# Cookie_Connector.net
KiCad netlist of a schematic drawn in Altium Designer
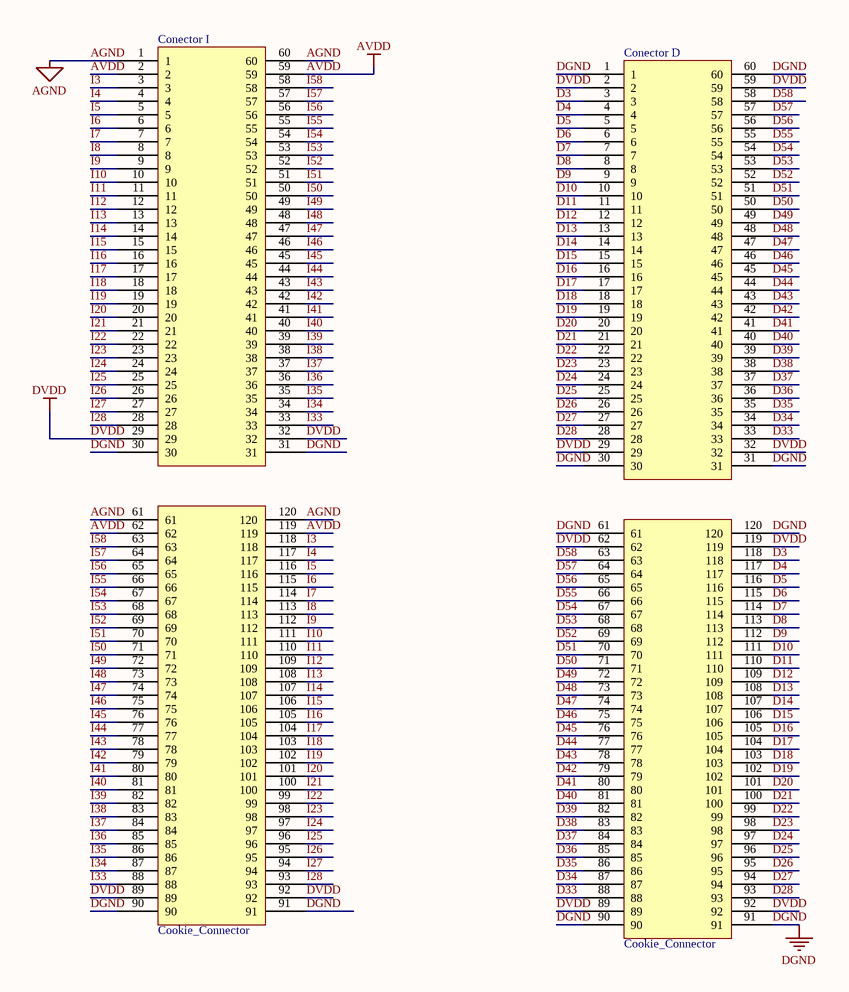
[diagram p0: Cookie Connector.schdoc]

(export (version "E")
  (design (tool "Eeschema 10.0.6"))
  (components
    (comp (ref "Conector D")
      (value "Cookie_Connector")
      (footprint "COOKIECON_HEADER_AND_SOCKET")
      (libsource (lib "Schlib1") (part "Cookie_Connector"))
    )
    (comp (ref "Conector I")
      (value "Cookie_Connector")
      (footprint "COOKIECON_HEADER_AND_SOCKET")
      (libsource (lib "Schlib1") (part "Cookie_Connector"))
    )
  )
  (nets
    (net (code "1") (name "/D3") (class "Default")
      (node (ref "Conector D") (pin "118") (pinfunction "118_118") (pintype "passive"))
      (node (ref "Conector D") (pin "3") (pinfunction "3_3") (pintype "passive"))
    )
    (net (code "2") (name "/D4") (class "Default")
      (node (ref "Conector D") (pin "117") (pinfunction "117_117") (pintype "passive"))
      (node (ref "Conector D") (pin "4") (pinfunction "4_4") (pintype "passive"))
    )
    (net (code "3") (name "/D5") (class "Default")
      (node (ref "Conector D") (pin "116") (pinfunction "116_116") (pintype "passive"))
      (node (ref "Conector D") (pin "5") (pinfunction "5_5") (pintype "passive"))
    )
    (net (code "4") (name "/D6") (class "Default")
      (node (ref "Conector D") (pin "115") (pinfunction "115_115") (pintype "passive"))
      (node (ref "Conector D") (pin "6") (pinfunction "6_6") (pintype "passive"))
    )
    (net (code "5") (name "/D7") (class "Default")
      (node (ref "Conector D") (pin "114") (pinfunction "114_114") (pintype "passive"))
      (node (ref "Conector D") (pin "7") (pinfunction "7_7") (pintype "passive"))
    )
    (net (code "6") (name "/D8") (class "Default")
      (node (ref "Conector D") (pin "113") (pinfunction "113_113") (pintype "passive"))
      (node (ref "Conector D") (pin "8") (pinfunction "8_8") (pintype "passive"))
    )
    (net (code "7") (name "/D9") (class "Default")
      (node (ref "Conector D") (pin "112") (pinfunction "112_112") (pintype "passive"))
      (node (ref "Conector D") (pin "9") (pinfunction "9_9") (pintype "passive"))
    )
    (net (code "8") (name "/D10") (class "Default")
      (node (ref "Conector D") (pin "10") (pinfunction "10_10") (pintype "passive"))
      (node (ref "Conector D") (pin "111") (pinfunction "111_111") (pintype "passive"))
    )
    (net (code "9") (name "/D11") (class "Default")
      (node (ref "Conector D") (pin "11") (pinfunction "11_11") (pintype "passive"))
      (node (ref "Conector D") (pin "110") (pinfunction "110_110") (pintype "passive"))
    )
    (net (code "10") (name "/D12") (class "Default")
      (node (ref "Conector D") (pin "109") (pinfunction "109_109") (pintype "passive"))
      (node (ref "Conector D") (pin "12") (pinfunction "12_12") (pintype "passive"))
    )
    (net (code "11") (name "/D13") (class "Default")
      (node (ref "Conector D") (pin "108") (pinfunction "108_108") (pintype "passive"))
      (node (ref "Conector D") (pin "13") (pinfunction "13_13") (pintype "passive"))
    )
    (net (code "12") (name "/D14") (class "Default")
      (node (ref "Conector D") (pin "107") (pinfunction "107_107") (pintype "passive"))
      (node (ref "Conector D") (pin "14") (pinfunction "14_14") (pintype "passive"))
    )
    (net (code "13") (name "/D15") (class "Default")
      (node (ref "Conector D") (pin "106") (pinfunction "106_106") (pintype "passive"))
      (node (ref "Conector D") (pin "15") (pinfunction "15_15") (pintype "passive"))
    )
    (net (code "14") (name "/D16") (class "Default")
      (node (ref "Conector D") (pin "105") (pinfunction "105_105") (pintype "passive"))
      (node (ref "Conector D") (pin "16") (pinfunction "16_16") (pintype "passive"))
    )
    (net (code "15") (name "/D17") (class "Default")
      (node (ref "Conector D") (pin "104") (pinfunction "104_104") (pintype "passive"))
      (node (ref "Conector D") (pin "17") (pinfunction "17_17") (pintype "passive"))
    )
    (net (code "16") (name "/D18") (class "Default")
      (node (ref "Conector D") (pin "103") (pinfunction "103_103") (pintype "passive"))
      (node (ref "Conector D") (pin "18") (pinfunction "18_18") (pintype "passive"))
    )
    (net (code "17") (name "/D19") (class "Default")
      (node (ref "Conector D") (pin "102") (pinfunction "102_102") (pintype "passive"))
      (node (ref "Conector D") (pin "19") (pinfunction "19_19") (pintype "passive"))
    )
    (net (code "18") (name "/D20") (class "Default")
      (node (ref "Conector D") (pin "101") (pinfunction "101_101") (pintype "passive"))
      (node (ref "Conector D") (pin "20") (pinfunction "20_20") (pintype "passive"))
    )
    (net (code "19") (name "/D21") (class "Default")
      (node (ref "Conector D") (pin "100") (pinfunction "100_100") (pintype "passive"))
      (node (ref "Conector D") (pin "21") (pinfunction "21_21") (pintype "passive"))
    )
    (net (code "20") (name "/D22") (class "Default")
      (node (ref "Conector D") (pin "22") (pinfunction "22_22") (pintype "passive"))
      (node (ref "Conector D") (pin "99") (pinfunction "99_99") (pintype "passive"))
    )
    (net (code "21") (name "/D23") (class "Default")
      (node (ref "Conector D") (pin "23") (pinfunction "23_23") (pintype "passive"))
      (node (ref "Conector D") (pin "98") (pinfunction "98_98") (pintype "passive"))
    )
    (net (code "22") (name "/D24") (class "Default")
      (node (ref "Conector D") (pin "24") (pinfunction "24_24") (pintype "passive"))
      (node (ref "Conector D") (pin "97") (pinfunction "97_97") (pintype "passive"))
    )
    (net (code "23") (name "/D25") (class "Default")
      (node (ref "Conector D") (pin "25") (pinfunction "25_25") (pintype "passive"))
      (node (ref "Conector D") (pin "96") (pinfunction "96_96") (pintype "passive"))
    )
    (net (code "24") (name "/D26") (class "Default")
      (node (ref "Conector D") (pin "26") (pinfunction "26_26") (pintype "passive"))
      (node (ref "Conector D") (pin "95") (pinfunction "95_95") (pintype "passive"))
    )
    (net (code "25") (name "/D27") (class "Default")
      (node (ref "Conector D") (pin "27") (pinfunction "27_27") (pintype "passive"))
      (node (ref "Conector D") (pin "94") (pinfunction "94_94") (pintype "passive"))
    )
    (net (code "26") (name "/D28") (class "Default")
      (node (ref "Conector D") (pin "28") (pinfunction "28_28") (pintype "passive"))
      (node (ref "Conector D") (pin "93") (pinfunction "93_93") (pintype "passive"))
    )
    (net (code "27") (name "/D33") (class "Default")
      (node (ref "Conector D") (pin "33") (pinfunction "33_33") (pintype "passive"))
      (node (ref "Conector D") (pin "88") (pinfunction "88_88") (pintype "passive"))
    )
    (net (code "28") (name "/D34") (class "Default")
      (node (ref "Conector D") (pin "34") (pinfunction "34_34") (pintype "passive"))
      (node (ref "Conector D") (pin "87") (pinfunction "87_87") (pintype "passive"))
    )
    (net (code "29") (name "/D35") (class "Default")
      (node (ref "Conector D") (pin "35") (pinfunction "35_35") (pintype "passive"))
      (node (ref "Conector D") (pin "86") (pinfunction "86_86") (pintype "passive"))
    )
    (net (code "30") (name "/D36") (class "Default")
      (node (ref "Conector D") (pin "36") (pinfunction "36_36") (pintype "passive"))
      (node (ref "Conector D") (pin "85") (pinfunction "85_85") (pintype "passive"))
    )
    (net (code "31") (name "/D37") (class "Default")
      (node (ref "Conector D") (pin "37") (pinfunction "37_37") (pintype "passive"))
      (node (ref "Conector D") (pin "84") (pinfunction "84_84") (pintype "passive"))
    )
    (net (code "32") (name "/D38") (class "Default")
      (node (ref "Conector D") (pin "38") (pinfunction "38_38") (pintype "passive"))
      (node (ref "Conector D") (pin "83") (pinfunction "83_83") (pintype "passive"))
    )
    (net (code "33") (name "/D39") (class "Default")
      (node (ref "Conector D") (pin "39") (pinfunction "39_39") (pintype "passive"))
      (node (ref "Conector D") (pin "82") (pinfunction "82_82") (pintype "passive"))
    )
    (net (code "34") (name "/D40") (class "Default")
      (node (ref "Conector D") (pin "40") (pinfunction "40_40") (pintype "passive"))
      (node (ref "Conector D") (pin "81") (pinfunction "81_81") (pintype "passive"))
    )
    (net (code "35") (name "/D41") (class "Default")
      (node (ref "Conector D") (pin "41") (pinfunction "41_41") (pintype "passive"))
      (node (ref "Conector D") (pin "80") (pinfunction "80_80") (pintype "passive"))
    )
    (net (code "36") (name "/D42") (class "Default")
      (node (ref "Conector D") (pin "42") (pinfunction "42_42") (pintype "passive"))
      (node (ref "Conector D") (pin "79") (pinfunction "79_79") (pintype "passive"))
    )
    (net (code "37") (name "/D43") (class "Default")
      (node (ref "Conector D") (pin "43") (pinfunction "43_43") (pintype "passive"))
      (node (ref "Conector D") (pin "78") (pinfunction "78_78") (pintype "passive"))
    )
    (net (code "38") (name "/D44") (class "Default")
      (node (ref "Conector D") (pin "44") (pinfunction "44_44") (pintype "passive"))
      (node (ref "Conector D") (pin "77") (pinfunction "77_77") (pintype "passive"))
    )
    (net (code "39") (name "/D45") (class "Default")
      (node (ref "Conector D") (pin "45") (pinfunction "45_45") (pintype "passive"))
      (node (ref "Conector D") (pin "76") (pinfunction "76_76") (pintype "passive"))
    )
    (net (code "40") (name "/D46") (class "Default")
      (node (ref "Conector D") (pin "46") (pinfunction "46_46") (pintype "passive"))
      (node (ref "Conector D") (pin "75") (pinfunction "75_75") (pintype "passive"))
    )
    (net (code "41") (name "/D47") (class "Default")
      (node (ref "Conector D") (pin "47") (pinfunction "47_47") (pintype "passive"))
      (node (ref "Conector D") (pin "74") (pinfunction "74_74") (pintype "passive"))
    )
    (net (code "42") (name "/D48") (class "Default")
      (node (ref "Conector D") (pin "48") (pinfunction "48_48") (pintype "passive"))
      (node (ref "Conector D") (pin "73") (pinfunction "73_73") (pintype "passive"))
    )
    (net (code "43") (name "/D49") (class "Default")
      (node (ref "Conector D") (pin "49") (pinfunction "49_49") (pintype "passive"))
      (node (ref "Conector D") (pin "72") (pinfunction "72_72") (pintype "passive"))
    )
    (net (code "44") (name "/D50") (class "Default")
      (node (ref "Conector D") (pin "50") (pinfunction "50_50") (pintype "passive"))
      (node (ref "Conector D") (pin "71") (pinfunction "71_71") (pintype "passive"))
    )
    (net (code "45") (name "/D51") (class "Default")
      (node (ref "Conector D") (pin "51") (pinfunction "51_51") (pintype "passive"))
      (node (ref "Conector D") (pin "70") (pinfunction "70_70") (pintype "passive"))
    )
    (net (code "46") (name "/D52") (class "Default")
      (node (ref "Conector D") (pin "52") (pinfunction "52_52") (pintype "passive"))
      (node (ref "Conector D") (pin "69") (pinfunction "69_69") (pintype "passive"))
    )
    (net (code "47") (name "/D53") (class "Default")
      (node (ref "Conector D") (pin "53") (pinfunction "53_53") (pintype "passive"))
      (node (ref "Conector D") (pin "68") (pinfunction "68_68") (pintype "passive"))
    )
    (net (code "48") (name "/D54") (class "Default")
      (node (ref "Conector D") (pin "54") (pinfunction "54_54") (pintype "passive"))
      (node (ref "Conector D") (pin "67") (pinfunction "67_67") (pintype "passive"))
    )
    (net (code "49") (name "/D55") (class "Default")
      (node (ref "Conector D") (pin "55") (pinfunction "55_55") (pintype "passive"))
      (node (ref "Conector D") (pin "66") (pinfunction "66_66") (pintype "passive"))
    )
    (net (code "50") (name "/D56") (class "Default")
      (node (ref "Conector D") (pin "56") (pinfunction "56_56") (pintype "passive"))
      (node (ref "Conector D") (pin "65") (pinfunction "65_65") (pintype "passive"))
    )
    (net (code "51") (name "/D57") (class "Default")
      (node (ref "Conector D") (pin "57") (pinfunction "57_57") (pintype "passive"))
      (node (ref "Conector D") (pin "64") (pinfunction "64_64") (pintype "passive"))
    )
    (net (code "52") (name "/D58") (class "Default")
      (node (ref "Conector D") (pin "58") (pinfunction "58_58") (pintype "passive"))
      (node (ref "Conector D") (pin "63") (pinfunction "63_63") (pintype "passive"))
    )
    (net (code "53") (name "/I3") (class "Default")
      (node (ref "Conector I") (pin "118") (pinfunction "118_118") (pintype "passive"))
      (node (ref "Conector I") (pin "3") (pinfunction "3_3") (pintype "passive"))
    )
    (net (code "54") (name "/I4") (class "Default")
      (node (ref "Conector I") (pin "117") (pinfunction "117_117") (pintype "passive"))
      (node (ref "Conector I") (pin "4") (pinfunction "4_4") (pintype "passive"))
    )
    (net (code "55") (name "/I5") (class "Default")
      (node (ref "Conector I") (pin "116") (pinfunction "116_116") (pintype "passive"))
      (node (ref "Conector I") (pin "5") (pinfunction "5_5") (pintype "passive"))
    )
    (net (code "56") (name "/I6") (class "Default")
      (node (ref "Conector I") (pin "115") (pinfunction "115_115") (pintype "passive"))
      (node (ref "Conector I") (pin "6") (pinfunction "6_6") (pintype "passive"))
    )
    (net (code "57") (name "/I7") (class "Default")
      (node (ref "Conector I") (pin "114") (pinfunction "114_114") (pintype "passive"))
      (node (ref "Conector I") (pin "7") (pinfunction "7_7") (pintype "passive"))
    )
    (net (code "58") (name "/I8") (class "Default")
      (node (ref "Conector I") (pin "113") (pinfunction "113_113") (pintype "passive"))
      (node (ref "Conector I") (pin "8") (pinfunction "8_8") (pintype "passive"))
    )
    (net (code "59") (name "/I9") (class "Default")
      (node (ref "Conector I") (pin "112") (pinfunction "112_112") (pintype "passive"))
      (node (ref "Conector I") (pin "9") (pinfunction "9_9") (pintype "passive"))
    )
    (net (code "60") (name "/I10") (class "Default")
      (node (ref "Conector I") (pin "10") (pinfunction "10_10") (pintype "passive"))
      (node (ref "Conector I") (pin "111") (pinfunction "111_111") (pintype "passive"))
    )
    (net (code "61") (name "/I11") (class "Default")
      (node (ref "Conector I") (pin "11") (pinfunction "11_11") (pintype "passive"))
      (node (ref "Conector I") (pin "110") (pinfunction "110_110") (pintype "passive"))
    )
    (net (code "62") (name "/I12") (class "Default")
      (node (ref "Conector I") (pin "109") (pinfunction "109_109") (pintype "passive"))
      (node (ref "Conector I") (pin "12") (pinfunction "12_12") (pintype "passive"))
    )
    (net (code "63") (name "/I13") (class "Default")
      (node (ref "Conector I") (pin "108") (pinfunction "108_108") (pintype "passive"))
      (node (ref "Conector I") (pin "13") (pinfunction "13_13") (pintype "passive"))
    )
    (net (code "64") (name "/I14") (class "Default")
      (node (ref "Conector I") (pin "107") (pinfunction "107_107") (pintype "passive"))
      (node (ref "Conector I") (pin "14") (pinfunction "14_14") (pintype "passive"))
    )
    (net (code "65") (name "/I15") (class "Default")
      (node (ref "Conector I") (pin "106") (pinfunction "106_106") (pintype "passive"))
      (node (ref "Conector I") (pin "15") (pinfunction "15_15") (pintype "passive"))
    )
    (net (code "66") (name "/I16") (class "Default")
      (node (ref "Conector I") (pin "105") (pinfunction "105_105") (pintype "passive"))
      (node (ref "Conector I") (pin "16") (pinfunction "16_16") (pintype "passive"))
    )
    (net (code "67") (name "/I17") (class "Default")
      (node (ref "Conector I") (pin "104") (pinfunction "104_104") (pintype "passive"))
      (node (ref "Conector I") (pin "17") (pinfunction "17_17") (pintype "passive"))
    )
    (net (code "68") (name "/I18") (class "Default")
      (node (ref "Conector I") (pin "103") (pinfunction "103_103") (pintype "passive"))
      (node (ref "Conector I") (pin "18") (pinfunction "18_18") (pintype "passive"))
    )
    (net (code "69") (name "/I19") (class "Default")
      (node (ref "Conector I") (pin "102") (pinfunction "102_102") (pintype "passive"))
      (node (ref "Conector I") (pin "19") (pinfunction "19_19") (pintype "passive"))
    )
    (net (code "70") (name "/I20") (class "Default")
      (node (ref "Conector I") (pin "101") (pinfunction "101_101") (pintype "passive"))
      (node (ref "Conector I") (pin "20") (pinfunction "20_20") (pintype "passive"))
    )
    (net (code "71") (name "/I21") (class "Default")
      (node (ref "Conector I") (pin "100") (pinfunction "100_100") (pintype "passive"))
      (node (ref "Conector I") (pin "21") (pinfunction "21_21") (pintype "passive"))
    )
    (net (code "72") (name "/I22") (class "Default")
      (node (ref "Conector I") (pin "22") (pinfunction "22_22") (pintype "passive"))
      (node (ref "Conector I") (pin "99") (pinfunction "99_99") (pintype "passive"))
    )
    (net (code "73") (name "/I23") (class "Default")
      (node (ref "Conector I") (pin "23") (pinfunction "23_23") (pintype "passive"))
      (node (ref "Conector I") (pin "98") (pinfunction "98_98") (pintype "passive"))
    )
    (net (code "74") (name "/I24") (class "Default")
      (node (ref "Conector I") (pin "24") (pinfunction "24_24") (pintype "passive"))
      (node (ref "Conector I") (pin "97") (pinfunction "97_97") (pintype "passive"))
    )
    (net (code "75") (name "/I25") (class "Default")
      (node (ref "Conector I") (pin "25") (pinfunction "25_25") (pintype "passive"))
      (node (ref "Conector I") (pin "96") (pinfunction "96_96") (pintype "passive"))
    )
    (net (code "76") (name "/I26") (class "Default")
      (node (ref "Conector I") (pin "26") (pinfunction "26_26") (pintype "passive"))
      (node (ref "Conector I") (pin "95") (pinfunction "95_95") (pintype "passive"))
    )
    (net (code "77") (name "/I27") (class "Default")
      (node (ref "Conector I") (pin "27") (pinfunction "27_27") (pintype "passive"))
      (node (ref "Conector I") (pin "94") (pinfunction "94_94") (pintype "passive"))
    )
    (net (code "78") (name "/I28") (class "Default")
      (node (ref "Conector I") (pin "28") (pinfunction "28_28") (pintype "passive"))
      (node (ref "Conector I") (pin "93") (pinfunction "93_93") (pintype "passive"))
    )
    (net (code "79") (name "/I33") (class "Default")
      (node (ref "Conector I") (pin "33") (pinfunction "33_33") (pintype "passive"))
      (node (ref "Conector I") (pin "88") (pinfunction "88_88") (pintype "passive"))
    )
    (net (code "80") (name "/I34") (class "Default")
      (node (ref "Conector I") (pin "34") (pinfunction "34_34") (pintype "passive"))
      (node (ref "Conector I") (pin "87") (pinfunction "87_87") (pintype "passive"))
    )
    (net (code "81") (name "/I35") (class "Default")
      (node (ref "Conector I") (pin "35") (pinfunction "35_35") (pintype "passive"))
      (node (ref "Conector I") (pin "86") (pinfunction "86_86") (pintype "passive"))
    )
    (net (code "82") (name "/I36") (class "Default")
      (node (ref "Conector I") (pin "36") (pinfunction "36_36") (pintype "passive"))
      (node (ref "Conector I") (pin "85") (pinfunction "85_85") (pintype "passive"))
    )
    (net (code "83") (name "/I37") (class "Default")
      (node (ref "Conector I") (pin "37") (pinfunction "37_37") (pintype "passive"))
      (node (ref "Conector I") (pin "84") (pinfunction "84_84") (pintype "passive"))
    )
    (net (code "84") (name "/I38") (class "Default")
      (node (ref "Conector I") (pin "38") (pinfunction "38_38") (pintype "passive"))
      (node (ref "Conector I") (pin "83") (pinfunction "83_83") (pintype "passive"))
    )
    (net (code "85") (name "/I39") (class "Default")
      (node (ref "Conector I") (pin "39") (pinfunction "39_39") (pintype "passive"))
      (node (ref "Conector I") (pin "82") (pinfunction "82_82") (pintype "passive"))
    )
    (net (code "86") (name "/I40") (class "Default")
      (node (ref "Conector I") (pin "40") (pinfunction "40_40") (pintype "passive"))
      (node (ref "Conector I") (pin "81") (pinfunction "81_81") (pintype "passive"))
    )
    (net (code "87") (name "/I41") (class "Default")
      (node (ref "Conector I") (pin "41") (pinfunction "41_41") (pintype "passive"))
      (node (ref "Conector I") (pin "80") (pinfunction "80_80") (pintype "passive"))
    )
    (net (code "88") (name "/I42") (class "Default")
      (node (ref "Conector I") (pin "42") (pinfunction "42_42") (pintype "passive"))
      (node (ref "Conector I") (pin "79") (pinfunction "79_79") (pintype "passive"))
    )
    (net (code "89") (name "/I43") (class "Default")
      (node (ref "Conector I") (pin "43") (pinfunction "43_43") (pintype "passive"))
      (node (ref "Conector I") (pin "78") (pinfunction "78_78") (pintype "passive"))
    )
    (net (code "90") (name "/I44") (class "Default")
      (node (ref "Conector I") (pin "44") (pinfunction "44_44") (pintype "passive"))
      (node (ref "Conector I") (pin "77") (pinfunction "77_77") (pintype "passive"))
    )
    (net (code "91") (name "/I45") (class "Default")
      (node (ref "Conector I") (pin "45") (pinfunction "45_45") (pintype "passive"))
      (node (ref "Conector I") (pin "76") (pinfunction "76_76") (pintype "passive"))
    )
    (net (code "92") (name "/I46") (class "Default")
      (node (ref "Conector I") (pin "46") (pinfunction "46_46") (pintype "passive"))
      (node (ref "Conector I") (pin "75") (pinfunction "75_75") (pintype "passive"))
    )
    (net (code "93") (name "/I47") (class "Default")
      (node (ref "Conector I") (pin "47") (pinfunction "47_47") (pintype "passive"))
      (node (ref "Conector I") (pin "74") (pinfunction "74_74") (pintype "passive"))
    )
    (net (code "94") (name "/I48") (class "Default")
      (node (ref "Conector I") (pin "48") (pinfunction "48_48") (pintype "passive"))
      (node (ref "Conector I") (pin "73") (pinfunction "73_73") (pintype "passive"))
    )
    (net (code "95") (name "/I49") (class "Default")
      (node (ref "Conector I") (pin "49") (pinfunction "49_49") (pintype "passive"))
      (node (ref "Conector I") (pin "72") (pinfunction "72_72") (pintype "passive"))
    )
    (net (code "96") (name "/I50") (class "Default")
      (node (ref "Conector I") (pin "50") (pinfunction "50_50") (pintype "passive"))
      (node (ref "Conector I") (pin "71") (pinfunction "71_71") (pintype "passive"))
    )
    (net (code "97") (name "/I51") (class "Default")
      (node (ref "Conector I") (pin "51") (pinfunction "51_51") (pintype "passive"))
      (node (ref "Conector I") (pin "70") (pinfunction "70_70") (pintype "passive"))
    )
    (net (code "98") (name "/I52") (class "Default")
      (node (ref "Conector I") (pin "52") (pinfunction "52_52") (pintype "passive"))
      (node (ref "Conector I") (pin "69") (pinfunction "69_69") (pintype "passive"))
    )
    (net (code "99") (name "/I53") (class "Default")
      (node (ref "Conector I") (pin "53") (pinfunction "53_53") (pintype "passive"))
      (node (ref "Conector I") (pin "68") (pinfunction "68_68") (pintype "passive"))
    )
    (net (code "100") (name "/I54") (class "Default")
      (node (ref "Conector I") (pin "54") (pinfunction "54_54") (pintype "passive"))
      (node (ref "Conector I") (pin "67") (pinfunction "67_67") (pintype "passive"))
    )
    (net (code "101") (name "/I55") (class "Default")
      (node (ref "Conector I") (pin "55") (pinfunction "55_55") (pintype "passive"))
      (node (ref "Conector I") (pin "66") (pinfunction "66_66") (pintype "passive"))
    )
    (net (code "102") (name "/I56") (class "Default")
      (node (ref "Conector I") (pin "56") (pinfunction "56_56") (pintype "passive"))
      (node (ref "Conector I") (pin "65") (pinfunction "65_65") (pintype "passive"))
    )
    (net (code "103") (name "/I57") (class "Default")
      (node (ref "Conector I") (pin "57") (pinfunction "57_57") (pintype "passive"))
      (node (ref "Conector I") (pin "64") (pinfunction "64_64") (pintype "passive"))
    )
    (net (code "104") (name "/I58") (class "Default")
      (node (ref "Conector I") (pin "58") (pinfunction "58_58") (pintype "passive"))
      (node (ref "Conector I") (pin "63") (pinfunction "63_63") (pintype "passive"))
    )
    (net (code "105") (name "AGND") (class "Default")
      (node (ref "Conector I") (pin "1") (pinfunction "1_1") (pintype "passive"))
      (node (ref "Conector I") (pin "120") (pinfunction "120_120") (pintype "passive"))
      (node (ref "Conector I") (pin "60") (pinfunction "60_60") (pintype "passive"))
      (node (ref "Conector I") (pin "61") (pinfunction "61_61") (pintype "passive"))
    )
    (net (code "106") (name "AVDD") (class "Default")
      (node (ref "Conector I") (pin "119") (pinfunction "119_119") (pintype "passive"))
      (node (ref "Conector I") (pin "2") (pinfunction "2_2") (pintype "passive"))
      (node (ref "Conector I") (pin "59") (pinfunction "59_59") (pintype "passive"))
      (node (ref "Conector I") (pin "62") (pinfunction "62_62") (pintype "passive"))
    )
    (net (code "107") (name "DGND") (class "Default")
      (node (ref "Conector D") (pin "1") (pinfunction "1_1") (pintype "passive"))
      (node (ref "Conector D") (pin "120") (pinfunction "120_120") (pintype "passive"))
      (node (ref "Conector D") (pin "30") (pinfunction "30_30") (pintype "passive"))
      (node (ref "Conector D") (pin "31") (pinfunction "31_31") (pintype "passive"))
      (node (ref "Conector D") (pin "60") (pinfunction "60_60") (pintype "passive"))
      (node (ref "Conector D") (pin "61") (pinfunction "61_61") (pintype "passive"))
      (node (ref "Conector D") (pin "90") (pinfunction "90_90") (pintype "passive"))
      (node (ref "Conector D") (pin "91") (pinfunction "91_91") (pintype "passive"))
      (node (ref "Conector I") (pin "30") (pinfunction "30_30") (pintype "passive"))
      (node (ref "Conector I") (pin "31") (pinfunction "31_31") (pintype "passive"))
      (node (ref "Conector I") (pin "90") (pinfunction "90_90") (pintype "passive"))
      (node (ref "Conector I") (pin "91") (pinfunction "91_91") (pintype "passive"))
    )
    (net (code "108") (name "DVDD") (class "Default")
      (node (ref "Conector D") (pin "119") (pinfunction "119_119") (pintype "passive"))
      (node (ref "Conector D") (pin "2") (pinfunction "2_2") (pintype "passive"))
      (node (ref "Conector D") (pin "29") (pinfunction "29_29") (pintype "passive"))
      (node (ref "Conector D") (pin "32") (pinfunction "32_32") (pintype "passive"))
      (node (ref "Conector D") (pin "59") (pinfunction "59_59") (pintype "passive"))
      (node (ref "Conector D") (pin "62") (pinfunction "62_62") (pintype "passive"))
      (node (ref "Conector D") (pin "89") (pinfunction "89_89") (pintype "passive"))
      (node (ref "Conector D") (pin "92") (pinfunction "92_92") (pintype "passive"))
      (node (ref "Conector I") (pin "29") (pinfunction "29_29") (pintype "passive"))
      (node (ref "Conector I") (pin "32") (pinfunction "32_32") (pintype "passive"))
      (node (ref "Conector I") (pin "89") (pinfunction "89_89") (pintype "passive"))
      (node (ref "Conector I") (pin "92") (pinfunction "92_92") (pintype "passive"))
    )
  )
)
